# motordrive2.net
KiCad netlist of a schematic drawn in EAGLE
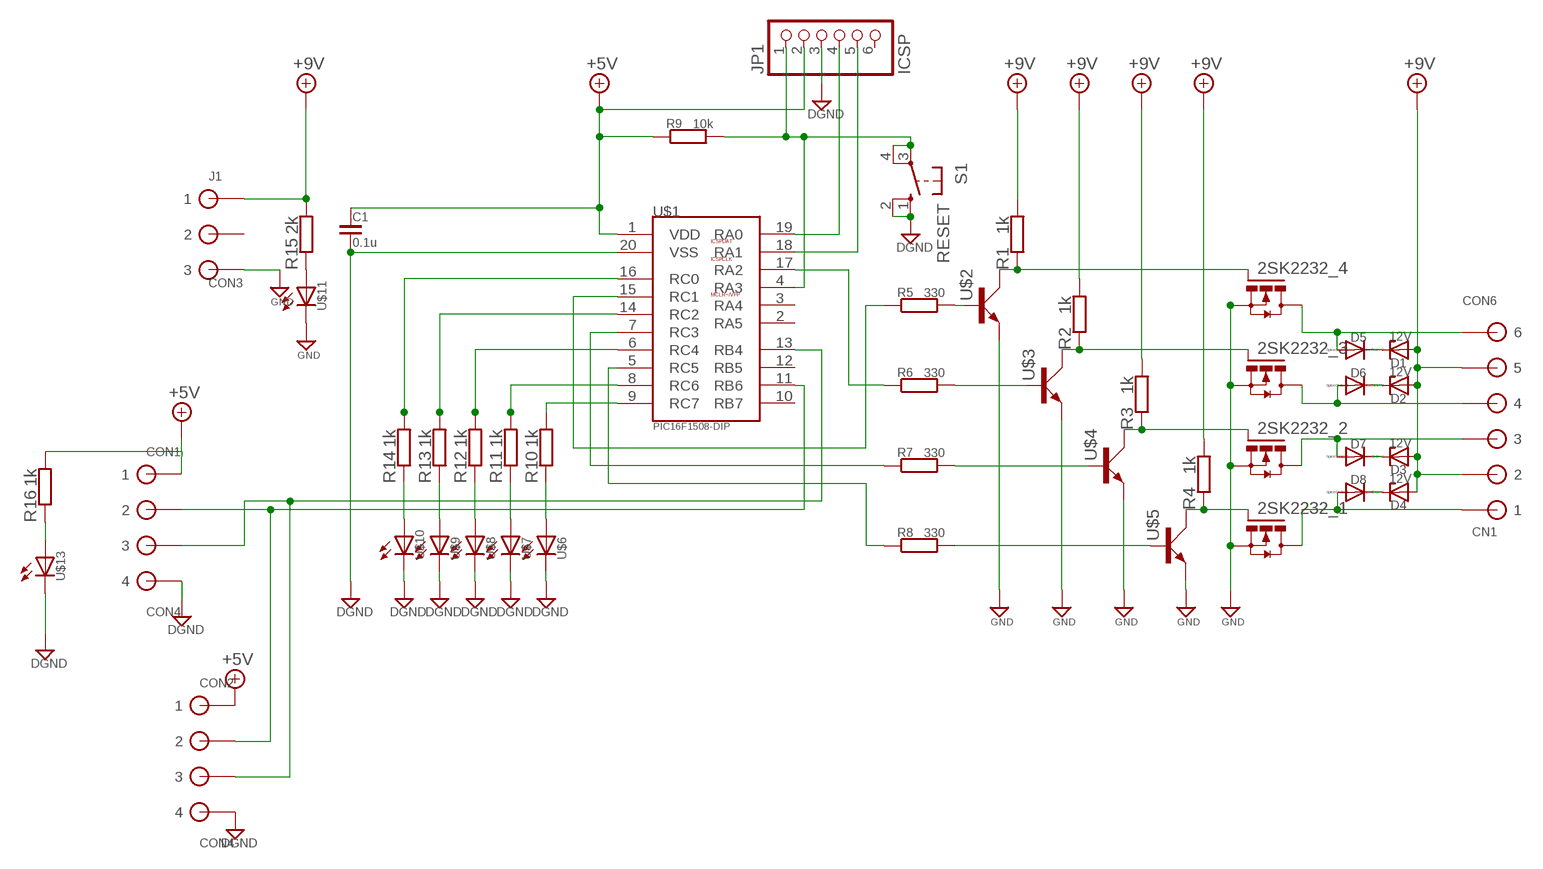
[diagram p0: schematic, sheet 1]

(export (version "E")
  (design (tool "Eeschema 10.0.6"))
  (components
    (comp (ref "2SK2232_1")
      (value "TO-220(MOS-FET_N)")
      (footprint "eagle-import:TO-220")
      (libsource (lib "eagle-import") (part "TO-220(MOS-FET_N)"))
    )
    (comp (ref "2SK2232_2")
      (value "TO-220(MOS-FET_N)")
      (footprint "eagle-import:TO-220")
      (libsource (lib "eagle-import") (part "TO-220(MOS-FET_N)"))
    )
    (comp (ref "2SK2232_3")
      (value "TO-220(MOS-FET_N)")
      (footprint "eagle-import:TO-220")
      (libsource (lib "eagle-import") (part "TO-220(MOS-FET_N)"))
    )
    (comp (ref "2SK2232_4")
      (value "TO-220(MOS-FET_N)")
      (footprint "eagle-import:TO-220")
      (libsource (lib "eagle-import") (part "TO-220(MOS-FET_N)"))
    )
    (comp (ref "C1")
      (value "0.1u")
      (footprint "eagle-import:C075-032X103")
      (libsource (lib "eagle-import") (part "(コンデンサ)セラミック075-032X103"))
    )
    (comp (ref "CN1")
      (value "CON6")
      (footprint "eagle-import:CON6")
      (libsource (lib "eagle-import") (part "CON6"))
    )
    (comp (ref "CON1")
      (value "CON4")
      (footprint "eagle-import:CON4")
      (libsource (lib "eagle-import") (part "CON4"))
    )
    (comp (ref "CON2")
      (value "CON4")
      (footprint "eagle-import:CON4")
      (libsource (lib "eagle-import") (part "CON4"))
    )
    (comp (ref "D1")
      (value "12V")
      (footprint "eagle-import:DO41Z(D=3)")
      (libsource (lib "eagle-import") (part "(汎用)ツェナーダイオードD=3"))
    )
    (comp (ref "D2")
      (value "12V")
      (footprint "eagle-import:DO41Z(D=3)")
      (libsource (lib "eagle-import") (part "(汎用)ツェナーダイオードD=3"))
    )
    (comp (ref "D3")
      (value "12V")
      (footprint "eagle-import:DO41Z(D=3)")
      (libsource (lib "eagle-import") (part "(汎用)ツェナーダイオードD=3"))
    )
    (comp (ref "D4")
      (value "12V")
      (footprint "eagle-import:DO41Z(D=3)")
      (libsource (lib "eagle-import") (part "(汎用)ツェナーダイオードD=3"))
    )
    (comp (ref "D5")
      (value "(汎用)D=3")
      (footprint "eagle-import:DO41(D=3)")
      (libsource (lib "eagle-import") (part "(汎用)D=3"))
    )
    (comp (ref "D6")
      (value "(汎用)D=3")
      (footprint "eagle-import:DO41(D=3)")
      (libsource (lib "eagle-import") (part "(汎用)D=3"))
    )
    (comp (ref "D7")
      (value "(汎用)D=3")
      (footprint "eagle-import:DO41(D=3)")
      (libsource (lib "eagle-import") (part "(汎用)D=3"))
    )
    (comp (ref "D8")
      (value "(汎用)D=3")
      (footprint "eagle-import:DO41(D=3)")
      (libsource (lib "eagle-import") (part "(汎用)D=3"))
    )
    (comp (ref "J1")
      (value "CON3")
      (footprint "eagle-import:CON3")
      (libsource (lib "eagle-import") (part "CON3"))
    )
    (comp (ref "JP1")
      (value "ICSP")
      (footprint "eagle-import:1X06")
      (libsource (lib "eagle-import") (part "PINHD-1X6"))
    )
    (comp (ref "R1")
      (value "1k")
      (footprint "eagle-import:0207_10")
      (libsource (lib "eagle-import") (part "抵抗(新JIS)0207/10"))
    )
    (comp (ref "R2")
      (value "1k")
      (footprint "eagle-import:0207_10")
      (libsource (lib "eagle-import") (part "抵抗(新JIS)0207/10"))
    )
    (comp (ref "R3")
      (value "1k")
      (footprint "eagle-import:0207_10")
      (libsource (lib "eagle-import") (part "抵抗(新JIS)0207/10"))
    )
    (comp (ref "R4")
      (value "1k")
      (footprint "eagle-import:0207_10")
      (libsource (lib "eagle-import") (part "抵抗(新JIS)0207/10"))
    )
    (comp (ref "R5")
      (value "330")
      (footprint "eagle-import:1_4W-H4_(0207_10)")
      (libsource (lib "eagle-import") (part "抵抗0207/10"))
    )
    (comp (ref "R6")
      (value "330")
      (footprint "eagle-import:1_4W-H4_(0207_10)")
      (libsource (lib "eagle-import") (part "抵抗0207/10"))
    )
    (comp (ref "R7")
      (value "330")
      (footprint "eagle-import:1_4W-H4_(0207_10)")
      (libsource (lib "eagle-import") (part "抵抗0207/10"))
    )
    (comp (ref "R8")
      (value "330")
      (footprint "eagle-import:1_4W-H4_(0207_10)")
      (libsource (lib "eagle-import") (part "抵抗0207/10"))
    )
    (comp (ref "R9")
      (value "10k")
      (footprint "eagle-import:1_4W-H4_(0207_10)")
      (libsource (lib "eagle-import") (part "抵抗0207/10"))
    )
    (comp (ref "R10")
      (value "1k")
      (footprint "eagle-import:0207_10")
      (libsource (lib "eagle-import") (part "抵抗(新JIS)0207/10"))
    )
    (comp (ref "R11")
      (value "1k")
      (footprint "eagle-import:0207_10")
      (libsource (lib "eagle-import") (part "抵抗(新JIS)0207/10"))
    )
    (comp (ref "R12")
      (value "1k")
      (footprint "eagle-import:0207_10")
      (libsource (lib "eagle-import") (part "抵抗(新JIS)0207/10"))
    )
    (comp (ref "R13")
      (value "1k")
      (footprint "eagle-import:0207_10")
      (libsource (lib "eagle-import") (part "抵抗(新JIS)0207/10"))
    )
    (comp (ref "R14")
      (value "1k")
      (footprint "eagle-import:0207_10")
      (libsource (lib "eagle-import") (part "抵抗(新JIS)0207/10"))
    )
    (comp (ref "R15")
      (value "2k")
      (footprint "eagle-import:0207_10")
      (libsource (lib "eagle-import") (part "抵抗(新JIS)0207/10"))
    )
    (comp (ref "R16")
      (value "1k")
      (footprint "eagle-import:0207_10")
      (libsource (lib "eagle-import") (part "抵抗(新JIS)0207/10"))
    )
    (comp (ref "S1")
      (value "RESET")
      (footprint "eagle-import:B3F-10XX")
      (fields (field (name "MPN") "B3F-1000"))
      (libsource (lib "eagle-import") (part "ノーマル4ピンタクトスイッチ"))
    )
    (comp (ref "U$1")
      (value "PIC16F1508-DIP")
      (footprint "eagle-import:DIP254P762X533-20")
      (libsource (lib "eagle-import") (part "PIC16F1508-DIP"))
    )
    (comp (ref "U$2")
      (value "TO-92(TRANSISTER_NPN)")
      (footprint "eagle-import:TO-92")
      (libsource (lib "eagle-import") (part "TO-92(TRANSISTER_NPN)"))
    )
    (comp (ref "U$3")
      (value "TO-92(TRANSISTER_NPN)")
      (footprint "eagle-import:TO-92")
      (libsource (lib "eagle-import") (part "TO-92(TRANSISTER_NPN)"))
    )
    (comp (ref "U$4")
      (value "TO-92(TRANSISTER_NPN)")
      (footprint "eagle-import:TO-92")
      (libsource (lib "eagle-import") (part "TO-92(TRANSISTER_NPN)"))
    )
    (comp (ref "U$5")
      (value "TO-92(TRANSISTER_NPN)")
      (footprint "eagle-import:TO-92")
      (libsource (lib "eagle-import") (part "TO-92(TRANSISTER_NPN)"))
    )
    (comp (ref "U$6")
      (value "LED(砲弾型)5")
      (footprint "eagle-import:LED5MM")
      (libsource (lib "eagle-import") (part "LED(砲弾型)5"))
    )
    (comp (ref "U$7")
      (value "LED(砲弾型)5")
      (footprint "eagle-import:LED5MM")
      (libsource (lib "eagle-import") (part "LED(砲弾型)5"))
    )
    (comp (ref "U$8")
      (value "LED(砲弾型)5")
      (footprint "eagle-import:LED5MM")
      (libsource (lib "eagle-import") (part "LED(砲弾型)5"))
    )
    (comp (ref "U$9")
      (value "LED(砲弾型)5")
      (footprint "eagle-import:LED5MM")
      (libsource (lib "eagle-import") (part "LED(砲弾型)5"))
    )
    (comp (ref "U$10")
      (value "LED(砲弾型)5")
      (footprint "eagle-import:LED5MM")
      (libsource (lib "eagle-import") (part "LED(砲弾型)5"))
    )
    (comp (ref "U$11")
      (value "LED(砲弾型)5")
      (footprint "eagle-import:LED5MM")
      (libsource (lib "eagle-import") (part "LED(砲弾型)5"))
    )
    (comp (ref "U$13")
      (value "LED(砲弾型)5")
      (footprint "eagle-import:LED5MM")
      (libsource (lib "eagle-import") (part "LED(砲弾型)5"))
    )
  )
  (nets
    (net (code "1") (name "+5V") (class "Default")
      (node (ref "C1") (pin "1") (pinfunction "1_1") (pintype "passive"))
      (node (ref "CON1") (pin "P$1") (pinfunction "1_P$1") (pintype "bidirectional"))
      (node (ref "CON2") (pin "P$1") (pinfunction "1_P$1") (pintype "bidirectional"))
      (node (ref "JP1") (pin "2") (pinfunction "2_2") (pintype "passive"))
      (node (ref "R16") (pin "2") (pinfunction "2_2") (pintype "passive"))
      (node (ref "R9") (pin "1") (pinfunction "1_1") (pintype "passive"))
      (node (ref "U$1") (pin "1") (pinfunction "VDD_1") (pintype "bidirectional"))
    )
    (net (code "2") (name "+9V") (class "Default")
      (node (ref "CN1") (pin "P$2") (pinfunction "2_P$2") (pintype "bidirectional"))
      (node (ref "CN1") (pin "P$5") (pinfunction "5_P$5") (pintype "bidirectional"))
      (node (ref "D1") (pin "A") (pinfunction "A_A") (pintype "passive"))
      (node (ref "D2") (pin "A") (pinfunction "A_A") (pintype "passive"))
      (node (ref "D3") (pin "A") (pinfunction "A_A") (pintype "passive"))
      (node (ref "D4") (pin "A") (pinfunction "A_A") (pintype "passive"))
      (node (ref "J1") (pin "P$1") (pinfunction "1_P$1") (pintype "bidirectional"))
      (node (ref "R1") (pin "2") (pinfunction "2_2") (pintype "passive"))
      (node (ref "R15") (pin "2") (pinfunction "2_2") (pintype "passive"))
      (node (ref "R2") (pin "2") (pinfunction "2_2") (pintype "passive"))
      (node (ref "R3") (pin "2") (pinfunction "2_2") (pintype "passive"))
      (node (ref "R4") (pin "2") (pinfunction "2_2") (pintype "passive"))
    )
    (net (code "3") (name "DGND") (class "Default")
      (node (ref "C1") (pin "2") (pinfunction "2_2") (pintype "passive"))
      (node (ref "CON1") (pin "P$4") (pinfunction "4_P$4") (pintype "bidirectional"))
      (node (ref "CON2") (pin "P$4") (pinfunction "4_P$4") (pintype "bidirectional"))
      (node (ref "JP1") (pin "3") (pinfunction "3_3") (pintype "passive"))
      (node (ref "S1") (pin "1") (pinfunction "S_1") (pintype "passive"))
      (node (ref "S1") (pin "2") (pinfunction "S1_2") (pintype "passive"))
      (node (ref "U$1") (pin "20") (pinfunction "VSS_20") (pintype "bidirectional"))
      (node (ref "U$10") (pin "K") (pinfunction "K_K") (pintype "passive"))
      (node (ref "U$13") (pin "K") (pinfunction "K_K") (pintype "passive"))
      (node (ref "U$6") (pin "K") (pinfunction "K_K") (pintype "passive"))
      (node (ref "U$7") (pin "K") (pinfunction "K_K") (pintype "passive"))
      (node (ref "U$8") (pin "K") (pinfunction "K_K") (pintype "passive"))
      (node (ref "U$9") (pin "K") (pinfunction "K_K") (pintype "passive"))
    )
    (net (code "4") (name "GND") (class "Default")
      (node (ref "2SK2232_1") (pin "3") (pinfunction "S_3") (pintype "passive"))
      (node (ref "2SK2232_2") (pin "3") (pinfunction "S_3") (pintype "passive"))
      (node (ref "2SK2232_3") (pin "3") (pinfunction "S_3") (pintype "passive"))
      (node (ref "2SK2232_4") (pin "3") (pinfunction "S_3") (pintype "passive"))
      (node (ref "J1") (pin "P$3") (pinfunction "3_P$3") (pintype "bidirectional"))
      (node (ref "U$11") (pin "K") (pinfunction "K_K") (pintype "passive"))
      (node (ref "U$2") (pin "1") (pinfunction "E_1") (pintype "passive"))
      (node (ref "U$3") (pin "1") (pinfunction "E_1") (pintype "passive"))
      (node (ref "U$4") (pin "1") (pinfunction "E_1") (pintype "passive"))
      (node (ref "U$5") (pin "1") (pinfunction "E_1") (pintype "passive"))
    )
    (net (code "5") (name "Net-(2SK2232_1-D)") (class "Default")
      (node (ref "2SK2232_1") (pin "2") (pinfunction "D_2") (pintype "passive"))
      (node (ref "CN1") (pin "P$1") (pinfunction "1_P$1") (pintype "bidirectional"))
      (node (ref "D8") (pin "A") (pinfunction "A_A") (pintype "passive"))
    )
    (net (code "6") (name "Net-(2SK2232_1-G)") (class "Default")
      (node (ref "2SK2232_1") (pin "1") (pinfunction "G_1") (pintype "passive"))
      (node (ref "R4") (pin "1") (pinfunction "1_1") (pintype "passive"))
      (node (ref "U$5") (pin "2") (pinfunction "C_2") (pintype "passive"))
    )
    (net (code "7") (name "Net-(2SK2232_2-D)") (class "Default")
      (node (ref "2SK2232_2") (pin "2") (pinfunction "D_2") (pintype "passive"))
      (node (ref "CN1") (pin "P$3") (pinfunction "3_P$3") (pintype "bidirectional"))
      (node (ref "D7") (pin "A") (pinfunction "A_A") (pintype "passive"))
    )
    (net (code "8") (name "Net-(2SK2232_2-G)") (class "Default")
      (node (ref "2SK2232_2") (pin "1") (pinfunction "G_1") (pintype "passive"))
      (node (ref "R3") (pin "1") (pinfunction "1_1") (pintype "passive"))
      (node (ref "U$4") (pin "2") (pinfunction "C_2") (pintype "passive"))
    )
    (net (code "9") (name "Net-(2SK2232_3-D)") (class "Default")
      (node (ref "2SK2232_3") (pin "2") (pinfunction "D_2") (pintype "passive"))
      (node (ref "CN1") (pin "P$4") (pinfunction "4_P$4") (pintype "bidirectional"))
      (node (ref "D6") (pin "A") (pinfunction "A_A") (pintype "passive"))
    )
    (net (code "10") (name "Net-(2SK2232_3-G)") (class "Default")
      (node (ref "2SK2232_3") (pin "1") (pinfunction "G_1") (pintype "passive"))
      (node (ref "R2") (pin "1") (pinfunction "1_1") (pintype "passive"))
      (node (ref "U$3") (pin "2") (pinfunction "C_2") (pintype "passive"))
    )
    (net (code "11") (name "Net-(2SK2232_4-D)") (class "Default")
      (node (ref "2SK2232_4") (pin "2") (pinfunction "D_2") (pintype "passive"))
      (node (ref "CN1") (pin "P$6") (pinfunction "6_P$6") (pintype "bidirectional"))
      (node (ref "D5") (pin "A") (pinfunction "A_A") (pintype "passive"))
    )
    (net (code "12") (name "Net-(2SK2232_4-G)") (class "Default")
      (node (ref "2SK2232_4") (pin "1") (pinfunction "G_1") (pintype "passive"))
      (node (ref "R1") (pin "1") (pinfunction "1_1") (pintype "passive"))
      (node (ref "U$2") (pin "2") (pinfunction "C_2") (pintype "passive"))
    )
    (net (code "13") (name "Net-(CON1-2)") (class "Default")
      (node (ref "CON1") (pin "P$2") (pinfunction "2_P$2") (pintype "bidirectional"))
      (node (ref "CON2") (pin "P$2") (pinfunction "2_P$2") (pintype "bidirectional"))
      (node (ref "U$1") (pin "11") (pinfunction "RB6_11") (pintype "bidirectional"))
    )
    (net (code "14") (name "Net-(CON1-3)") (class "Default")
      (node (ref "CON1") (pin "P$3") (pinfunction "3_P$3") (pintype "bidirectional"))
      (node (ref "CON2") (pin "P$3") (pinfunction "3_P$3") (pintype "bidirectional"))
      (node (ref "U$1") (pin "13") (pinfunction "RB4_13") (pintype "bidirectional"))
    )
    (net (code "15") (name "Net-(D1-PadC)") (class "Default")
      (node (ref "D1") (pin "C") (pinfunction "C_C") (pintype "passive"))
      (node (ref "D5") (pin "C") (pinfunction "C_C") (pintype "passive"))
    )
    (net (code "16") (name "Net-(D2-PadC)") (class "Default")
      (node (ref "D2") (pin "C") (pinfunction "C_C") (pintype "passive"))
      (node (ref "D6") (pin "C") (pinfunction "C_C") (pintype "passive"))
    )
    (net (code "17") (name "Net-(D3-PadC)") (class "Default")
      (node (ref "D3") (pin "C") (pinfunction "C_C") (pintype "passive"))
      (node (ref "D7") (pin "C") (pinfunction "C_C") (pintype "passive"))
    )
    (net (code "18") (name "Net-(D4-PadC)") (class "Default")
      (node (ref "D4") (pin "C") (pinfunction "C_C") (pintype "passive"))
      (node (ref "D8") (pin "C") (pinfunction "C_C") (pintype "passive"))
    )
    (net (code "19") (name "Net-(R10-Pad1)") (class "Default")
      (node (ref "R10") (pin "1") (pinfunction "1_1") (pintype "passive"))
      (node (ref "U$6") (pin "A") (pinfunction "A_A") (pintype "passive"))
    )
    (net (code "20") (name "Net-(R11-Pad1)") (class "Default")
      (node (ref "R11") (pin "1") (pinfunction "1_1") (pintype "passive"))
      (node (ref "U$7") (pin "A") (pinfunction "A_A") (pintype "passive"))
    )
    (net (code "21") (name "Net-(R12-Pad1)") (class "Default")
      (node (ref "R12") (pin "1") (pinfunction "1_1") (pintype "passive"))
      (node (ref "U$8") (pin "A") (pinfunction "A_A") (pintype "passive"))
    )
    (net (code "22") (name "Net-(R13-Pad1)") (class "Default")
      (node (ref "R13") (pin "1") (pinfunction "1_1") (pintype "passive"))
      (node (ref "U$9") (pin "A") (pinfunction "A_A") (pintype "passive"))
    )
    (net (code "23") (name "Net-(R14-Pad1)") (class "Default")
      (node (ref "R14") (pin "1") (pinfunction "1_1") (pintype "passive"))
      (node (ref "U$10") (pin "A") (pinfunction "A_A") (pintype "passive"))
    )
    (net (code "24") (name "Net-(R15-Pad1)") (class "Default")
      (node (ref "R15") (pin "1") (pinfunction "1_1") (pintype "passive"))
      (node (ref "U$11") (pin "A") (pinfunction "A_A") (pintype "passive"))
    )
    (net (code "25") (name "Net-(R16-Pad1)") (class "Default")
      (node (ref "R16") (pin "1") (pinfunction "1_1") (pintype "passive"))
      (node (ref "U$13") (pin "A") (pinfunction "A_A") (pintype "passive"))
    )
    (net (code "26") (name "Net-(S1-P)") (class "Default")
      (node (ref "JP1") (pin "1") (pinfunction "1_1") (pintype "passive"))
      (node (ref "R9") (pin "2") (pinfunction "2_2") (pintype "passive"))
      (node (ref "S1") (pin "3") (pinfunction "P_3") (pintype "passive"))
      (node (ref "S1") (pin "4") (pinfunction "P1_4") (pintype "passive"))
      (node (ref "U$1") (pin "4") (pinfunction "RA3_4") (pintype "bidirectional"))
    )
    (net (code "27") (name "Net-(U$1-RA0)") (class "Default")
      (node (ref "JP1") (pin "4") (pinfunction "4_4") (pintype "passive"))
      (node (ref "U$1") (pin "19") (pinfunction "RA0_19") (pintype "bidirectional"))
    )
    (net (code "28") (name "Net-(U$1-RA1)") (class "Default")
      (node (ref "JP1") (pin "5") (pinfunction "5_5") (pintype "passive"))
      (node (ref "U$1") (pin "18") (pinfunction "RA1_18") (pintype "bidirectional"))
    )
    (net (code "29") (name "Net-(U$1-RA2)") (class "Default")
      (node (ref "R6") (pin "1") (pinfunction "1_1") (pintype "passive"))
      (node (ref "U$1") (pin "17") (pinfunction "RA2_17") (pintype "bidirectional"))
    )
    (net (code "30") (name "Net-(U$1-RC0)") (class "Default")
      (node (ref "R14") (pin "2") (pinfunction "2_2") (pintype "passive"))
      (node (ref "U$1") (pin "16") (pinfunction "RC0_16") (pintype "bidirectional"))
    )
    (net (code "31") (name "Net-(U$1-RC1)") (class "Default")
      (node (ref "R5") (pin "1") (pinfunction "1_1") (pintype "passive"))
      (node (ref "U$1") (pin "15") (pinfunction "RC1_15") (pintype "bidirectional"))
    )
    (net (code "32") (name "Net-(U$1-RC2)") (class "Default")
      (node (ref "R13") (pin "2") (pinfunction "2_2") (pintype "passive"))
      (node (ref "U$1") (pin "14") (pinfunction "RC2_14") (pintype "bidirectional"))
    )
    (net (code "33") (name "Net-(U$1-RC3)") (class "Default")
      (node (ref "R7") (pin "1") (pinfunction "1_1") (pintype "passive"))
      (node (ref "U$1") (pin "7") (pinfunction "RC3_7") (pintype "bidirectional"))
    )
    (net (code "34") (name "Net-(U$1-RC4)") (class "Default")
      (node (ref "R12") (pin "2") (pinfunction "2_2") (pintype "passive"))
      (node (ref "U$1") (pin "6") (pinfunction "RC4_6") (pintype "bidirectional"))
    )
    (net (code "35") (name "Net-(U$1-RC5)") (class "Default")
      (node (ref "R8") (pin "1") (pinfunction "1_1") (pintype "passive"))
      (node (ref "U$1") (pin "5") (pinfunction "RC5_5") (pintype "bidirectional"))
    )
    (net (code "36") (name "Net-(U$1-RC6)") (class "Default")
      (node (ref "R11") (pin "2") (pinfunction "2_2") (pintype "passive"))
      (node (ref "U$1") (pin "8") (pinfunction "RC6_8") (pintype "bidirectional"))
    )
    (net (code "37") (name "Net-(U$1-RC7)") (class "Default")
      (node (ref "R10") (pin "2") (pinfunction "2_2") (pintype "passive"))
      (node (ref "U$1") (pin "9") (pinfunction "RC7_9") (pintype "bidirectional"))
    )
    (net (code "38") (name "Net-(U$2-B)") (class "Default")
      (node (ref "R5") (pin "2") (pinfunction "2_2") (pintype "passive"))
      (node (ref "U$2") (pin "3") (pinfunction "B_3") (pintype "passive"))
    )
    (net (code "39") (name "Net-(U$3-B)") (class "Default")
      (node (ref "R6") (pin "2") (pinfunction "2_2") (pintype "passive"))
      (node (ref "U$3") (pin "3") (pinfunction "B_3") (pintype "passive"))
    )
    (net (code "40") (name "Net-(U$4-B)") (class "Default")
      (node (ref "R7") (pin "2") (pinfunction "2_2") (pintype "passive"))
      (node (ref "U$4") (pin "3") (pinfunction "B_3") (pintype "passive"))
    )
    (net (code "41") (name "Net-(U$5-B)") (class "Default")
      (node (ref "R8") (pin "2") (pinfunction "2_2") (pintype "passive"))
      (node (ref "U$5") (pin "3") (pinfunction "B_3") (pintype "passive"))
    )
    (net (code "42") (name "unconnected-(J1-2-PadP$2)") (class "Default")
      (node (ref "J1") (pin "P$2") (pinfunction "2_P$2") (pintype "bidirectional"))
    )
    (net (code "43") (name "unconnected-(JP1-Pad6)") (class "Default")
      (node (ref "JP1") (pin "6") (pinfunction "6_6") (pintype "passive"))
    )
    (net (code "44") (name "unconnected-(U$1-RA4-Pad3)") (class "Default")
      (node (ref "U$1") (pin "3") (pinfunction "RA4_3") (pintype "bidirectional"))
    )
    (net (code "45") (name "unconnected-(U$1-RA5-Pad2)") (class "Default")
      (node (ref "U$1") (pin "2") (pinfunction "RA5_2") (pintype "bidirectional"))
    )
    (net (code "46") (name "unconnected-(U$1-RB5-Pad12)") (class "Default")
      (node (ref "U$1") (pin "12") (pinfunction "RB5_12") (pintype "bidirectional"))
    )
    (net (code "47") (name "unconnected-(U$1-RB7-Pad10)") (class "Default")
      (node (ref "U$1") (pin "10") (pinfunction "RB7_10") (pintype "bidirectional"))
    )
  )
)
